# 7-JTAG_Power.net
KiCad netlist of a schematic drawn in Altium Designer
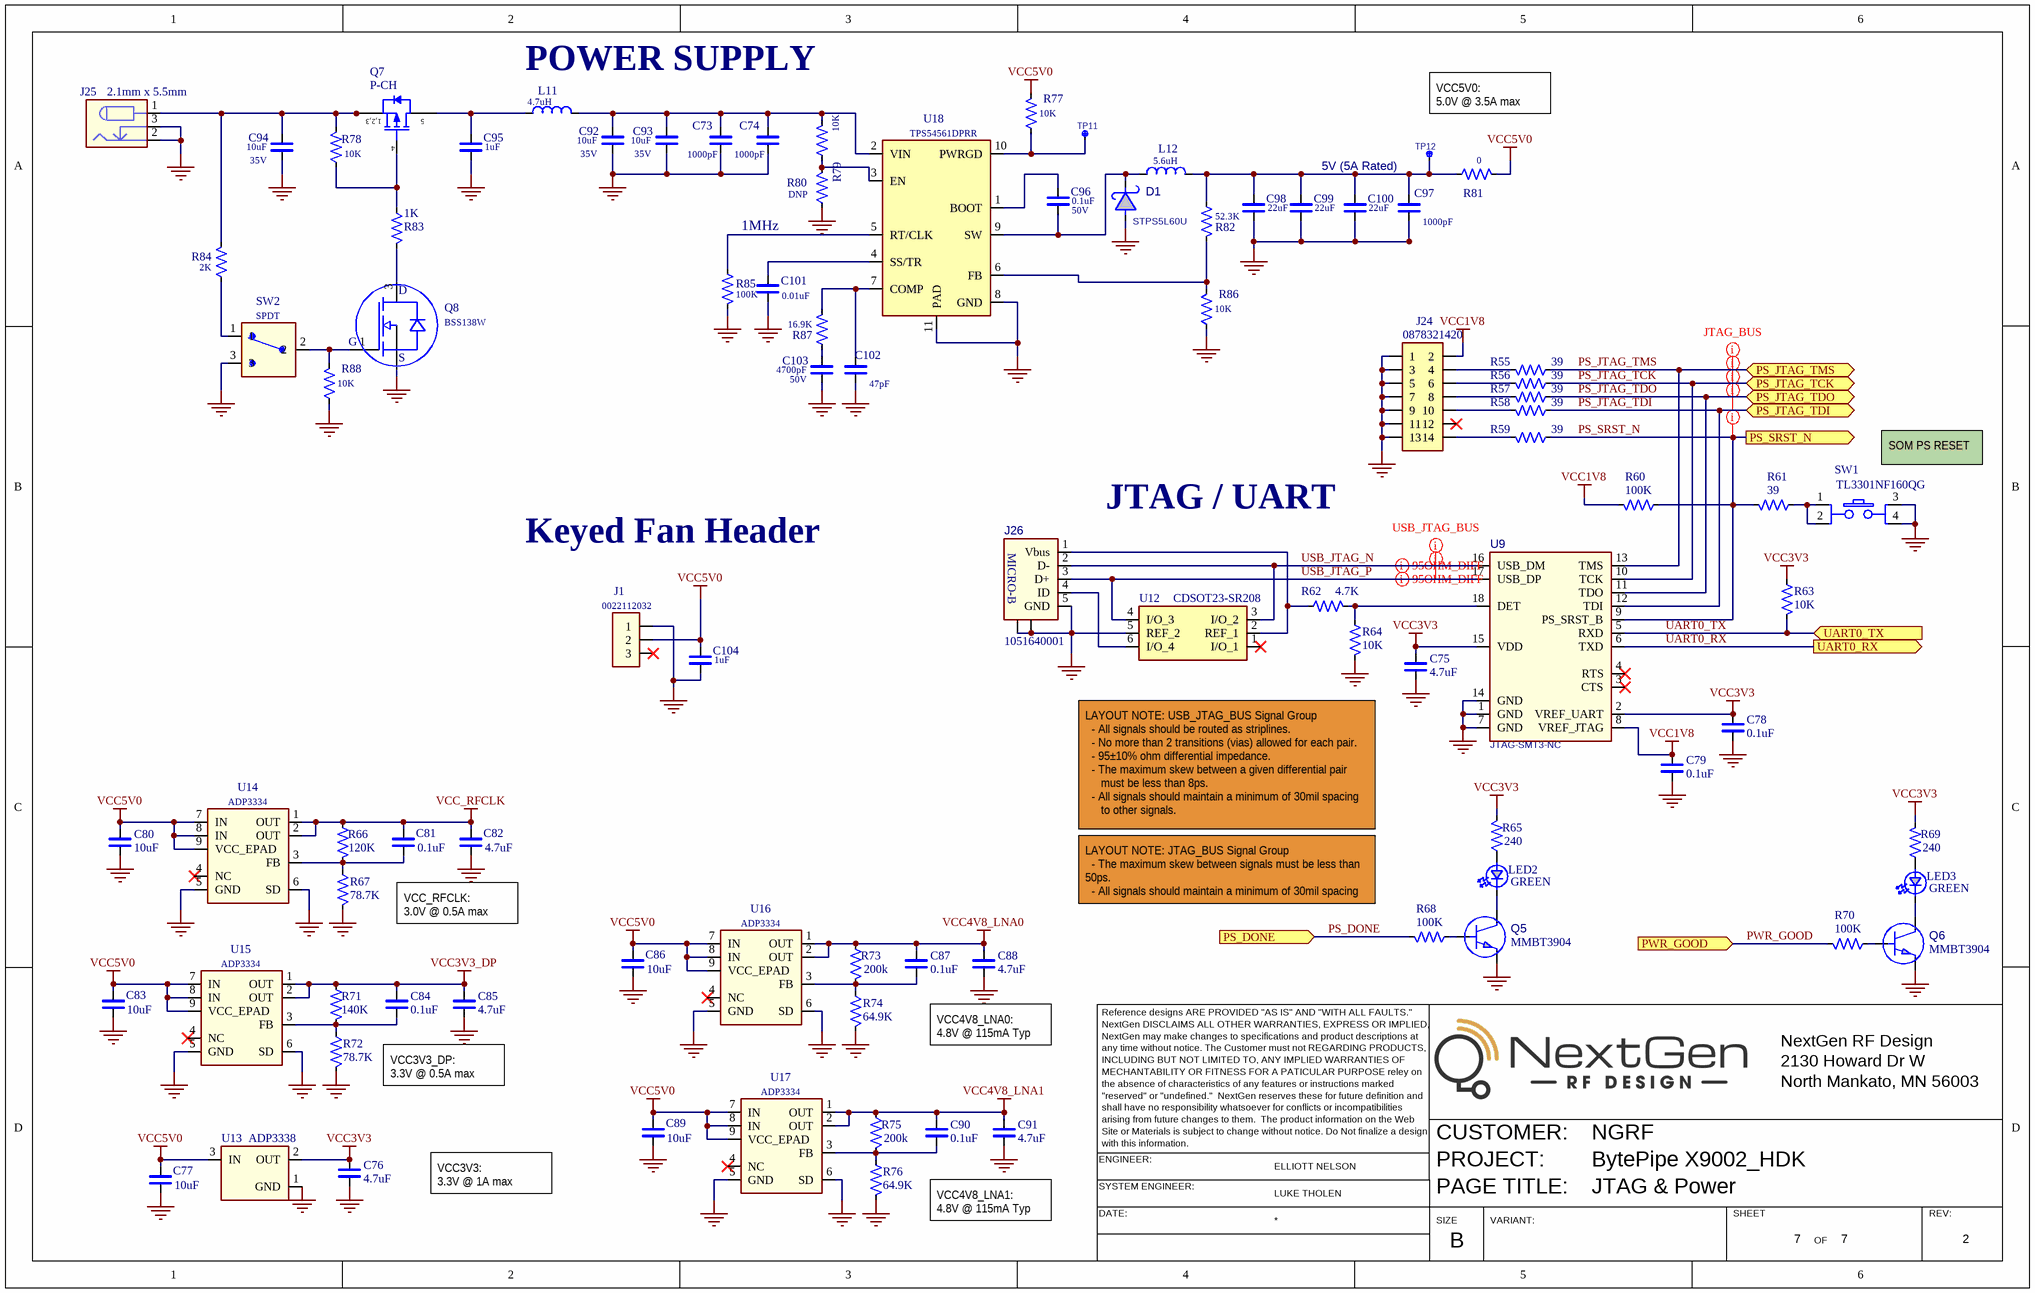
[diagram p0: 7-JTAG & Power.SchDoc]

(export (version "E")
  (design (tool "Eeschema 10.0.6"))
  (components
    (comp (ref "C73")
      (value "1000pF")
      (footprint "SM/0402/CAP")
      (description "CAP CER 1000PF 50V C0G/NP0 0402")
      (libsource (lib "NextGenRF_Symbols_SMT") (part "CAP_CERAMIC_0402"))
    )
    (comp (ref "C74")
      (value "1000pF")
      (footprint "SM/0402/CAP")
      (description "CAP CER 1000PF 50V C0G/NP0 0402")
      (libsource (lib "NextGenRF_Symbols_SMT") (part "CAP_CERAMIC_0402"))
    )
    (comp (ref "C75")
      (value "4.7uF")
      (footprint "SM/0402/CAP")
      (description "CAP CER 4.7UF 10V X5R 0402")
      (fields (field (name "Comment") "CAP_CERAMIC_0402"))
      (libsource (lib "NextGenRF_Symbols_SMT") (part "CAP_CERAMIC_0402"))
    )
    (comp (ref "C76")
      (value "4.7uF")
      (footprint "SM/0402/CAP")
      (description "CAP CER 4.7UF 10V X5R 0402")
      (fields (field (name "Comment") "CAP_CERAMIC_0402"))
      (libsource (lib "NextGenRF_Symbols_SMT") (part "CAP_CERAMIC_0402"))
    )
    (comp (ref "C77")
      (value "10uF")
      (footprint "SM/0402/CAP")
      (description "10µF ±20% 10V Ceramic Capacitor X5R 0402 (1005 Metric)")
      (fields (field (name "Comment") "CAP_CERAMIC_0402"))
      (libsource (lib "NextGenRF_Symbols_SMT") (part "CAP_CERAMIC_0402"))
    )
    (comp (ref "C78")
      (value "0.1uF")
      (footprint "SM/0402/CAP")
      (description "CAP CER 0.1UF 25V X7R 0402")
      (fields (field (name "Comment") "CAP_CERAMIC_0402"))
      (libsource (lib "NextGenRF_Symbols_SMT") (part "CAP_CERAMIC_0402"))
    )
    (comp (ref "C79")
      (value "0.1uF")
      (footprint "SM/0402/CAP")
      (description "CAP CER 0.1UF 25V X7R 0402")
      (fields (field (name "Comment") "CAP_CERAMIC_0402"))
      (libsource (lib "NextGenRF_Symbols_SMT") (part "CAP_CERAMIC_0402"))
    )
    (comp (ref "C80")
      (value "10uF")
      (footprint "SM/0402/CAP")
      (description "10µF ±20% 10V Ceramic Capacitor X5R 0402 (1005 Metric)")
      (fields (field (name "Comment") "CAP_CERAMIC_0402"))
      (libsource (lib "NextGenRF_Symbols_SMT") (part "CAP_CERAMIC_0402"))
    )
    (comp (ref "C81")
      (value "0.1uF")
      (footprint "SM/0402/CAP")
      (description "CAP CER 0.1UF 25V X7R 0402")
      (fields (field (name "Comment") "CAP_CERAMIC_0402"))
      (libsource (lib "NextGenRF_Symbols_SMT") (part "CAP_CERAMIC_0402"))
    )
    (comp (ref "C82")
      (value "4.7uF")
      (footprint "SM/0402/CAP")
      (description "CAP CER 4.7UF 10V X5R 0402")
      (fields (field (name "Comment") "CAP_CERAMIC_0402"))
      (libsource (lib "NextGenRF_Symbols_SMT") (part "CAP_CERAMIC_0402"))
    )
    (comp (ref "C83")
      (value "10uF")
      (footprint "SM/0402/CAP")
      (description "10µF ±20% 10V Ceramic Capacitor X5R 0402 (1005 Metric)")
      (fields (field (name "Comment") "CAP_CERAMIC_0402"))
      (libsource (lib "NextGenRF_Symbols_SMT") (part "CAP_CERAMIC_0402"))
    )
    (comp (ref "C84")
      (value "0.1uF")
      (footprint "SM/0402/CAP")
      (description "CAP CER 0.1UF 25V X7R 0402")
      (fields (field (name "Comment") "CAP_CERAMIC_0402"))
      (libsource (lib "NextGenRF_Symbols_SMT") (part "CAP_CERAMIC_0402"))
    )
    (comp (ref "C85")
      (value "4.7uF")
      (footprint "SM/0402/CAP")
      (description "CAP CER 4.7UF 10V X5R 0402")
      (fields (field (name "Comment") "CAP_CERAMIC_0402"))
      (libsource (lib "NextGenRF_Symbols_SMT") (part "CAP_CERAMIC_0402"))
    )
    (comp (ref "C86")
      (value "10uF")
      (footprint "SM/0402/CAP")
      (description "10µF ±20% 10V Ceramic Capacitor X5R 0402 (1005 Metric)")
      (fields (field (name "Comment") "CAP_CERAMIC_0402"))
      (libsource (lib "NextGenRF_Symbols_SMT") (part "CAP_CERAMIC_0402"))
    )
    (comp (ref "C87")
      (value "0.1uF")
      (footprint "SM/0402/CAP")
      (description "CAP CER 0.1UF 25V X7R 0402")
      (fields (field (name "Comment") "CAP_CERAMIC_0402"))
      (libsource (lib "NextGenRF_Symbols_SMT") (part "CAP_CERAMIC_0402"))
    )
    (comp (ref "C88")
      (value "4.7uF")
      (footprint "SM/0402/CAP")
      (description "CAP CER 4.7UF 10V X5R 0402")
      (fields (field (name "Comment") "CAP_CERAMIC_0402"))
      (libsource (lib "NextGenRF_Symbols_SMT") (part "CAP_CERAMIC_0402"))
    )
    (comp (ref "C89")
      (value "10uF")
      (footprint "SM/0402/CAP")
      (description "10µF ±20% 10V Ceramic Capacitor X5R 0402 (1005 Metric)")
      (fields (field (name "Comment") "CAP_CERAMIC_0402"))
      (libsource (lib "NextGenRF_Symbols_SMT") (part "CAP_CERAMIC_0402"))
    )
    (comp (ref "C90")
      (value "0.1uF")
      (footprint "SM/0402/CAP")
      (description "CAP CER 0.1UF 25V X7R 0402")
      (fields (field (name "Comment") "CAP_CERAMIC_0402"))
      (libsource (lib "NextGenRF_Symbols_SMT") (part "CAP_CERAMIC_0402"))
    )
    (comp (ref "C91")
      (value "4.7uF")
      (footprint "SM/0402/CAP")
      (description "CAP CER 4.7UF 10V X5R 0402")
      (fields (field (name "Comment") "CAP_CERAMIC_0402"))
      (libsource (lib "NextGenRF_Symbols_SMT") (part "CAP_CERAMIC_0402"))
    )
    (comp (ref "C92")
      (value "10uF")
      (footprint "NGRF_SMT_Footprints:SM/0805/CAP")
      (description "CAP CER 10UF 35V X5R 0805")
      (fields (field (name "VOLT") "35V") (field (name "Comment") "CAP_CERAMIC_0805"))
      (libsource (lib "NextGenRF_Symbols_SMT") (part "CAP_CERAMIC_0805"))
    )
    (comp (ref "C93")
      (value "10uF")
      (footprint "NGRF_SMT_Footprints:SM/0805/CAP")
      (description "CAP CER 10UF 35V X5R 0805")
      (fields (field (name "VOLT") "35V") (field (name "Comment") "CAP_CERAMIC_0805"))
      (libsource (lib "NextGenRF_Symbols_SMT") (part "CAP_CERAMIC_0805"))
    )
    (comp (ref "C94")
      (value "10uF")
      (footprint "NGRF_SMT_Footprints:SM/0805/CAP")
      (description "CAP CER 10UF 35V X5R 0805")
      (fields (field (name "VOLT") "35V") (field (name "Comment") "CAP_CERAMIC_0805"))
      (libsource (lib "NextGenRF_Symbols_SMT") (part "CAP_CERAMIC_0805"))
    )
    (comp (ref "C95")
      (value "1uF")
      (footprint "NGRF_SMT_Footprints:SM/0603/CAP")
      (fields (field (name "Comment") "CAP_CERAMIC_0603"))
      (libsource (lib "NextGenRF_Symbols_SMT") (part "CAP_CERAMIC_0603"))
    )
    (comp (ref "C96")
      (value "0.1uF")
      (footprint "SM/0402/CAP")
      (description "CAP CER 0.1UF 50V X7R 0402")
      (fields (field (name "VOLT") "50V") (field (name "Comment") "CAP_CERAMIC_0402"))
      (libsource (lib "NextGenRF_Symbols_SMT") (part "CAP_CERAMIC_0402"))
    )
    (comp (ref "C97")
      (value "1000pF")
      (footprint "SM/0402/CAP")
      (description "CAP CER 1000PF 50V C0G/NP0 0402")
      (libsource (lib "NextGenRF_Symbols_SMT") (part "CAP_CERAMIC_0402"))
    )
    (comp (ref "C98")
      (value "22uF")
      (footprint "NGRF_SMT_Footprints:SM/0805/CAP")
      (description "CAP CER 22UF 16V X5R 0805")
      (fields (field (name "Comment") "CAP_CERAMIC_0805"))
      (libsource (lib "NextGenRF_Symbols_SMT") (part "CAP_CERAMIC_0805"))
    )
    (comp (ref "C99")
      (value "22uF")
      (footprint "NGRF_SMT_Footprints:SM/0805/CAP")
      (description "CAP CER 22UF 16V X5R 0805")
      (fields (field (name "Comment") "CAP_CERAMIC_0805"))
      (libsource (lib "NextGenRF_Symbols_SMT") (part "CAP_CERAMIC_0805"))
    )
    (comp (ref "C100")
      (value "22uF")
      (footprint "NGRF_SMT_Footprints:SM/0805/CAP")
      (description "CAP CER 22UF 16V X5R 0805")
      (fields (field (name "Comment") "CAP_CERAMIC_0805"))
      (libsource (lib "NextGenRF_Symbols_SMT") (part "CAP_CERAMIC_0805"))
    )
    (comp (ref "C101")
      (value "0.01uF")
      (footprint "SM/0402/CAP")
      (description "CAP CER 10000PF 50V X7R 0402")
      (libsource (lib "NextGenRF_Symbols_SMT") (part "CAP_CERAMIC_0402"))
    )
    (comp (ref "C102")
      (value "47pF")
      (footprint "SM/0402/CAP")
      (description "CAP CER 47PF 50V C0G/NP0 0402")
      (libsource (lib "NextGenRF_Symbols_SMT") (part "CAP_CERAMIC_0402"))
    )
    (comp (ref "C103")
      (value "4700pF")
      (footprint "SM/0402/CAP")
      (description "CAP CER 4700PF 50V X7R 0402")
      (fields (field (name "VOLT") "50V"))
      (libsource (lib "NextGenRF_Symbols_SMT") (part "CAP_CERAMIC_0402"))
    )
    (comp (ref "C104")
      (value "1uF")
      (footprint "NGRF_SMT_Footprints:SM/0603/CAP")
      (fields (field (name "Comment") "CAP_CERAMIC_0603"))
      (libsource (lib "NextGenRF_Symbols_SMT") (part "CAP_CERAMIC_0603"))
    )
    (comp (ref "D1")
      (value "STPS5L60U")
      (footprint "NGRF_SMT_Footprints:SM/DO-214AA/SMB_A")
      (description "DIODE SCHOTTKY 60V 5A SMB")
      (fields (field (name "Comment") "DIODE_SCHOTTKY SMB"))
      (libsource (lib "NextGenRF_Symbols_SMT") (part "DIODE_SCHOTTKY SMB"))
    )
    (comp (ref "J1")
      (value "0022112032")
      (footprint "CON/MLX/0022112032/3P")
      (description "Connector Header Through Hole 3 position 0.100\" (2.54mm).  Molex KK 100 Series.")
      (libsource (lib "NextGenRF_Symbols_TH") (part "CON_100SP_1X3P_MLX_KK100"))
    )
    (comp (ref "J24")
      (value "0878321420")
      (footprint "SM/CON/MLX/0878321420")
      (description "Connector Header Surface Mount 14 position 0.079\" (2.00mm)")
      (fields (field (name "Comment") "CON_MOLEX_0878321420_14P"))
      (libsource (lib "NextGenRF_Symbols_SMT") (part "CON_MOLEX_0878321420_14P"))
    )
    (comp (ref "J25")
      (value "2.1mm x 5.5mm")
      (footprint "NGRF_Thru-Hole_Footprints:CON/WURTH/694106301002")
      (description "Wurth DC power jack, 2.1mm pin, right angle")
      (fields (field (name "Comment") "CON_WURTH_694106301002"))
      (libsource (lib "NextGenRF_Symbols_TH") (part "CON_WURTH_694106301002"))
    )
    (comp (ref "J26")
      (value "1051640001")
      (footprint "SM/CON/USB/MICRO B RA")
      (description "USB MICRO-B RIGHT ANGLE, MOLEX 1051640001")
      (fields (field (name "Comment") "CON_USB_MICRO-B_RA"))
      (libsource (lib "NextGenRF_Symbols_SMT") (part "CON_USB_MICRO-B_RA"))
    )
    (comp (ref "L11")
      (value "4.7uH")
      (footprint "SM/IND/COILCRAFT/XAL4020")
      (description "Fixed Inductors 4.7uH 20% 5.1A 44.1mOhms AEC-Q200")
      (fields (field (name "Comment") "IND_COILCRAFT_XAL4020"))
      (libsource (lib "NextGenRF_Symbols_SMT") (part "IND_COILCRAFT_XAL4020"))
    )
    (comp (ref "L12")
      (value "5.6uH")
      (footprint "SM/IND/COILCRAFT/XAL7030")
      (fields (field (name "Comment") "IND_COILCRAFT_XAL7030"))
      (libsource (lib "NextGenRF_Symbols_SMT") (part "IND_COILCRAFT_XAL7030"))
    )
    (comp (ref "LED2")
      (value "GREEN")
      (footprint "NGRF_SMT_Footprints:SM/LED_0603")
      (description "LED-0603")
      (fields (field (name "Comment") "LED_0603"))
      (libsource (lib "NextGenRF_Symbols_SMT") (part "LED_0603"))
    )
    (comp (ref "LED3")
      (value "GREEN")
      (footprint "NGRF_SMT_Footprints:SM/LED_0603")
      (description "LED-0603")
      (fields (field (name "Comment") "LED_0603"))
      (libsource (lib "NextGenRF_Symbols_SMT") (part "LED_0603"))
    )
    (comp (ref "Q5")
      (value "MMBT3904")
      (footprint "NGRF_SMT_Footprints:SM/SOT23_A")
      (description "Bipolar (BJT) Transistor NPN 40V 200mA 300MHz 300mW Surface Mount SOT-23-3 (TO-236)")
      (fields (field (name "Comment") "TRANSISTOR_NPN_SOT23"))
      (libsource (lib "NextGenRF_Symbols_SMT") (part "TRANSISTOR_NPN_SOT23"))
    )
    (comp (ref "Q6")
      (value "MMBT3904")
      (footprint "NGRF_SMT_Footprints:SM/SOT23_A")
      (description "Bipolar (BJT) Transistor NPN 40V 200mA 300MHz 300mW Surface Mount SOT-23-3 (TO-236)")
      (fields (field (name "Comment") "TRANSISTOR_NPN_SOT23"))
      (libsource (lib "NextGenRF_Symbols_SMT") (part "TRANSISTOR_NPN_SOT23"))
    )
    (comp (ref "Q7")
      (value "P-CH")
      (footprint "SM/POWERPAK/VISHAY/SO-8")
      (description "P-Channel 20 V 60A (Tc) 6.25W (Ta), 104W (Tc) Surface Mount PowerPAK® SO-8")
      (fields (field (name "Comment") "MOSFET P-CH 20V 60A PPAK SO-8"))
      (libsource (lib "NextGenRF_Symbols_SMT") (part "FET_P-CHANNEL_PPAK-SO-8"))
    )
    (comp (ref "Q8")
      (value "BSS138W")
      (footprint "SM/SOT323_A")
      (description "FET, N-Channel, SC70/SOT323")
      (fields (field (name "Comment") "FET_N-CHANNEL_SC70"))
      (libsource (lib "NextGenRF_Symbols_SMT") (part "FET_N-CHANNEL_SC70"))
    )
    (comp (ref "R55")
      (value "39")
      (footprint "SM/0402/RES")
      (description "RES SMD 39 OHM 1% 1/10W 0402")
      (fields (field (name "Comment") "RES_0402_A"))
      (libsource (lib "NextGenRF_Symbols_SMT") (part "RES_0402_A"))
    )
    (comp (ref "R56")
      (value "39")
      (footprint "SM/0402/RES")
      (description "RES SMD 39 OHM 1% 1/10W 0402")
      (fields (field (name "Comment") "RES_0402_A"))
      (libsource (lib "NextGenRF_Symbols_SMT") (part "RES_0402_A"))
    )
    (comp (ref "R57")
      (value "39")
      (footprint "SM/0402/RES")
      (description "RES SMD 39 OHM 1% 1/10W 0402")
      (fields (field (name "Comment") "RES_0402_A"))
      (libsource (lib "NextGenRF_Symbols_SMT") (part "RES_0402_A"))
    )
    (comp (ref "R58")
      (value "39")
      (footprint "SM/0402/RES")
      (description "RES SMD 39 OHM 1% 1/10W 0402")
      (fields (field (name "Comment") "RES_0402_A"))
      (libsource (lib "NextGenRF_Symbols_SMT") (part "RES_0402_A"))
    )
    (comp (ref "R59")
      (value "39")
      (footprint "SM/0402/RES")
      (description "RES SMD 39 OHM 1% 1/10W 0402")
      (fields (field (name "Comment") "RES_0402_A"))
      (libsource (lib "NextGenRF_Symbols_SMT") (part "RES_0402_A"))
    )
    (comp (ref "R60")
      (value "100K")
      (footprint "SM/0402/RES")
      (description "RES SMD 100K OHM 1% 1/10W 0402")
      (fields (field (name "Comment") "RES_0402_A"))
      (libsource (lib "NextGenRF_Symbols_SMT") (part "RES_0402_A"))
    )
    (comp (ref "R61")
      (value "39")
      (footprint "SM/0402/RES")
      (description "RES SMD 39 OHM 1% 1/10W 0402")
      (fields (field (name "Comment") "RES_0402_A"))
      (libsource (lib "NextGenRF_Symbols_SMT") (part "RES_0402_A"))
    )
    (comp (ref "R62")
      (value "4.7K")
      (footprint "SM/0402/RES")
      (description "RES SMD 4.7K OHM 1% 1/10W 0402")
      (fields (field (name "Comment") "RES_0402_A"))
      (libsource (lib "NextGenRF_Symbols_SMT") (part "RES_0402_A"))
    )
    (comp (ref "R63")
      (value "10K")
      (footprint "SM/0402/RES")
      (fields (field (name "Comment") "RES_0402_A"))
      (libsource (lib "NextGenRF_Symbols_SMT") (part "RES_0402_A"))
    )
    (comp (ref "R64")
      (value "10K")
      (footprint "SM/0402/RES")
      (fields (field (name "Comment") "RES_0402_A"))
      (libsource (lib "NextGenRF_Symbols_SMT") (part "RES_0402_A"))
    )
    (comp (ref "R65")
      (value "240")
      (footprint "SM/0402/RES")
      (description "RES SMD 240 OHM 1% 1/10W 0402")
      (fields (field (name "Comment") "RES_0402_A"))
      (libsource (lib "NextGenRF_Symbols_SMT") (part "RES_0402_A"))
    )
    (comp (ref "R66")
      (value "120K")
      (footprint "SM/0402/RES")
      (description "RES 120K OHM 1% 1/10W 0402 SMD")
      (fields (field (name "Comment") "RES_0402_A"))
      (libsource (lib "NextGenRF_Symbols_SMT") (part "RES_0402_A"))
    )
    (comp (ref "R67")
      (value "78.7K")
      (footprint "SM/0402/RES")
      (description "RES SMD 78.7K OHM 1% 1/10W 0402")
      (fields (field (name "Comment") "RES_0402_A"))
      (libsource (lib "NextGenRF_Symbols_SMT") (part "RES_0402_A"))
    )
    (comp (ref "R68")
      (value "100K")
      (footprint "SM/0402/RES")
      (description "RES SMD 100K OHM 1% 1/10W 0402")
      (fields (field (name "Comment") "RES_0402_A"))
      (libsource (lib "NextGenRF_Symbols_SMT") (part "RES_0402_A"))
    )
    (comp (ref "R69")
      (value "240")
      (footprint "SM/0402/RES")
      (description "RES SMD 240 OHM 1% 1/10W 0402")
      (fields (field (name "Comment") "RES_0402_A"))
      (libsource (lib "NextGenRF_Symbols_SMT") (part "RES_0402_A"))
    )
    (comp (ref "R70")
      (value "100K")
      (footprint "SM/0402/RES")
      (description "RES SMD 100K OHM 1% 1/10W 0402")
      (fields (field (name "Comment") "RES_0402_A"))
      (libsource (lib "NextGenRF_Symbols_SMT") (part "RES_0402_A"))
    )
    (comp (ref "R71")
      (value "140K")
      (footprint "SM/0402/RES")
      (description "RES SMD 140K OHM 1% 1/10W 0402")
      (fields (field (name "Comment") "RES_0402_A"))
      (libsource (lib "NextGenRF_Symbols_SMT") (part "RES_0402_A"))
    )
    (comp (ref "R72")
      (value "78.7K")
      (footprint "SM/0402/RES")
      (description "RES SMD 78.7K OHM 1% 1/10W 0402")
      (fields (field (name "Comment") "RES_0402_A"))
      (libsource (lib "NextGenRF_Symbols_SMT") (part "RES_0402_A"))
    )
    (comp (ref "R73")
      (value "200k")
      (footprint "SM/0402/RES")
      (description "RES SMD 200K OHM 1% 1/10W 0402")
      (fields (field (name "Comment") "RES_0402_A"))
      (libsource (lib "NextGenRF_Symbols_SMT") (part "RES_0402_A"))
    )
    (comp (ref "R74")
      (value "64.9K")
      (footprint "SM/0402/RES")
      (description "RES SMD 64.9K OHM 1% 1/10W 0402")
      (fields (field (name "Comment") "RES_0402_A"))
      (libsource (lib "NextGenRF_Symbols_SMT") (part "RES_0402_A"))
    )
    (comp (ref "R75")
      (value "200k")
      (footprint "SM/0402/RES")
      (description "RES SMD 200K OHM 1% 1/10W 0402")
      (fields (field (name "Comment") "RES_0402_A"))
      (libsource (lib "NextGenRF_Symbols_SMT") (part "RES_0402_A"))
    )
    (comp (ref "R76")
      (value "64.9K")
      (footprint "SM/0402/RES")
      (description "RES SMD 64.9K OHM 1% 1/10W 0402")
      (fields (field (name "Comment") "RES_0402_A"))
      (libsource (lib "NextGenRF_Symbols_SMT") (part "RES_0402_A"))
    )
    (comp (ref "R77")
      (value "10K")
      (footprint "SM/0402/RES")
      (description "RES SMD 10K OHM 1% 1/10W 0402")
      (fields (field (name "Comment") "RES_0402_A"))
      (libsource (lib "NextGenRF_Symbols_SMT") (part "RES_0402_A"))
    )
    (comp (ref "R78")
      (value "10K")
      (footprint "SM/0402/RES")
      (description "RES SMD 10K OHM 1% 1/10W 0402")
      (fields (field (name "Comment") "RES_0402_A"))
      (libsource (lib "NextGenRF_Symbols_SMT") (part "RES_0402_A"))
    )
    (comp (ref "R79")
      (value "10K")
      (footprint "SM/0402/RES")
      (description "RES SMD 10K OHM 1% 1/10W 0402")
      (fields (field (name "Comment") "RES_0402_A"))
      (libsource (lib "NextGenRF_Symbols_SMT") (part "RES_0402_A"))
    )
    (comp (ref "R80")
      (value "DNP")
      (footprint "SM/0402/RES")
      (fields (field (name "Comment") "RES_0402_A"))
      (libsource (lib "NextGenRF_Symbols_SMT") (part "RES_0402_A"))
    )
    (comp (ref "R81")
      (value "0")
      (footprint "NGRF_SMT_Footprints:SM/0805/RES")
      (description "RES SMD 0 OHM JUMPER 1/8W 0805")
      (fields (field (name "Comment") "RES_0805_A"))
      (libsource (lib "NextGenRF_Symbols_SMT") (part "RES_0805_A"))
    )
    (comp (ref "R82")
      (value "52.3K")
      (footprint "SM/0402/RES")
      (description "RES SMD 52.3K OHM 1% 1/10W 0402")
      (fields (field (name "Comment") "RES_0402_A"))
      (libsource (lib "NextGenRF_Symbols_SMT") (part "RES_0402_A"))
    )
    (comp (ref "R83")
      (value "1K")
      (footprint "SM/0402/RES")
      (description "RES SMD 1K OHM 1% 1/10W 0402")
      (fields (field (name "Comment") "RES_0402_A"))
      (libsource (lib "NextGenRF_Symbols_SMT") (part "RES_0402_A"))
    )
    (comp (ref "R84")
      (value "2K")
      (footprint "SM/0402/RES")
      (description "RES SMD 2 KOHM 1% 1/5W 0402")
      (fields (field (name "Comment") "RES_0402_A"))
      (libsource (lib "NextGenRF_Symbols_SMT") (part "RES_0402_A"))
    )
    (comp (ref "R85")
      (value "100K")
      (footprint "SM/0402/RES")
      (description "RES SMD 100K OHM 1% 1/10W 0402")
      (fields (field (name "Comment") "RES_0402_A"))
      (libsource (lib "NextGenRF_Symbols_SMT") (part "RES_0402_A"))
    )
    (comp (ref "R86")
      (value "10K")
      (footprint "SM/0402/RES")
      (description "RES SMD 10K OHM 1% 1/10W 0402")
      (fields (field (name "Comment") "RES_0402_A"))
      (libsource (lib "NextGenRF_Symbols_SMT") (part "RES_0402_A"))
    )
    (comp (ref "R87")
      (value "16.9K")
      (footprint "SM/0402/RES")
      (description "RES SMD 16.9K OHM 1% 1/10W 0402")
      (fields (field (name "Comment") "RES_0402_A"))
      (libsource (lib "NextGenRF_Symbols_SMT") (part "RES_0402_A"))
    )
    (comp (ref "R88")
      (value "10K")
      (footprint "SM/0402/RES")
      (description "RES SMD 10K OHM 1% 1/10W 0402")
      (fields (field (name "Comment") "RES_0402_A"))
      (libsource (lib "NextGenRF_Symbols_SMT") (part "RES_0402_A"))
    )
    (comp (ref "SW1")
      (value "TL3301NF160QG")
      (footprint "SM/SWITCH/E-SWITCH/SPST")
      (description "Tactile Switch SPST-NO Top Actuated Surface Mount")
      (fields (field (name "Comment") "SWITCH_E-SWITCH_TACTILE_SPST"))
      (libsource (lib "NextGenRF_Symbols_SMT") (part "SWITCH_E-SWITCH_TACTILE_SPST"))
    )
    (comp (ref "SW2")
      (value "SPDT")
      (footprint "SWITCH/NIDEC/SPDT/AS1D-2M-10-Z")
      (description "SWITCH SLIDE SPDT 50MA 48V")
      (fields (field (name "Comment") "AS1D-2M-10-Z"))
      (libsource (lib "NextGenRF_Symbols_TH") (part "SWITCH_SLIDE_NIDEC_SPDT"))
    )
    (comp (ref "TP11")
      (value "TESTPOINT_030")
      (footprint "SM/TESTPOINT/30MIL")
      (libsource (lib "NextGenRF_Symbols_SMT") (part "TESTPOINT_030"))
    )
    (comp (ref "TP12")
      (value "TESTPOINT_030")
      (footprint "SM/TESTPOINT/30MIL")
      (libsource (lib "NextGenRF_Symbols_SMT") (part "TESTPOINT_030"))
    )
    (comp (ref "U9")
      (value "JTAG-SMT3-NC")
      (footprint "SM/MODULE/DIGILENT/JTAG-SMT3")
      (description "SMT Programming module for Xilinx FPGAs.")
      (fields (field (name "Comment") "MODULE_JTAG-SMT3-NC_18P"))
      (libsource (lib "NextGenRF_Symbols_SMT") (part "MODULE_JTAG-SMT3-NC_18P"))
    )
    (comp (ref "U12")
      (value "CDSOT23-SR208")
      (footprint "SM/SOT23-6_C")
      (description "Clamp Ipp Tvs Diode Surface Mount SOT-23-6.")
      (fields (field (name "Comment") "TVS_CDSOT23_SOT23-6_C"))
      (libsource (lib "NextGenRF_Symbols_SMT") (part "TVS_CDSOT23_SOT23-6_C"))
    )
    (comp (ref "U13")
      (value "ADP3338")
      (footprint "SM/SOT223-3_B")
      (description "Linear Voltage Regulator IC 3.3V Output 1A SOT-223-3")
      (fields (field (name "Comment") "REG_ADP3338_SOT223-3"))
      (libsource (lib "NextGenRF_Symbols_SMT") (part "REG_ADP3338_SOT223-3"))
    )
    (comp (ref "U14")
      (value "ADP3334")
      (footprint "SM/DFN8/3x3MM_B")
      (description "Linear Voltage Regulator IC  1 Output  500mA 8-LFCSP-WD (3x3)")
      (fields (field (name "Comment") "REG_ADP334_DFN-8"))
      (libsource (lib "NextGenRF_Symbols_SMT") (part "REG_ADP334_DFN-8"))
    )
    (comp (ref "U15")
      (value "ADP3334")
      (footprint "SM/DFN8/3x3MM_B")
      (description "Linear Voltage Regulator IC  1 Output  500mA 8-LFCSP-WD (3x3)")
      (fields (field (name "Comment") "REG_ADP334_DFN-8"))
      (libsource (lib "NextGenRF_Symbols_SMT") (part "REG_ADP334_DFN-8"))
    )
    (comp (ref "U16")
      (value "ADP3334")
      (footprint "SM/DFN8/3x3MM_B")
      (description "Linear Voltage Regulator IC  1 Output  500mA 8-LFCSP-WD (3x3)")
      (fields (field (name "Comment") "REG_ADP334_DFN-8"))
      (libsource (lib "NextGenRF_Symbols_SMT") (part "REG_ADP334_DFN-8"))
    )
    (comp (ref "U17")
      (value "ADP3334")
      (footprint "SM/DFN8/3x3MM_B")
      (description "Linear Voltage Regulator IC  1 Output  500mA 8-LFCSP-WD (3x3)")
      (fields (field (name "Comment") "REG_ADP334_DFN-8"))
      (libsource (lib "NextGenRF_Symbols_SMT") (part "REG_ADP334_DFN-8"))
    )
    (comp (ref "U18")
      (value "TPS54561DPRR")
      (footprint "SM/WSON10/4x4MM_A")
      (description "4.5-V to 60-V Input, 5-A, Step-Down DC-DC Converter with Soft-Start and Eco-mode")
      (fields (field (name "Comment") "REG_TPS54561_WSON-10"))
      (libsource (lib "NextGenRF_Symbols_SMT") (part "REG_TPS54561_WSON-10"))
    )
  )
  (nets
    (net (code "1") (name "/PS_DONE") (class "Default")
      (node (ref "R68") (pin "2") (pinfunction "2_2") (pintype "passive"))
    )
    (net (code "2") (name "/PS_JTAG_TCK") (class "Default")
      (node (ref "R56") (pin "1") (pinfunction "1_1") (pintype "passive"))
      (node (ref "U9") (pin "10") (pinfunction "TCK_10") (pintype "passive"))
    )
    (net (code "3") (name "/PS_JTAG_TDI") (class "Default")
      (node (ref "R58") (pin "1") (pinfunction "1_1") (pintype "passive"))
      (node (ref "U9") (pin "12") (pinfunction "TDI_12") (pintype "passive"))
    )
    (net (code "4") (name "/PS_JTAG_TDO") (class "Default")
      (node (ref "R57") (pin "1") (pinfunction "1_1") (pintype "passive"))
      (node (ref "U9") (pin "11") (pinfunction "TDO_11") (pintype "passive"))
    )
    (net (code "5") (name "/PS_JTAG_TMS") (class "Default")
      (node (ref "R55") (pin "1") (pinfunction "1_1") (pintype "passive"))
      (node (ref "U9") (pin "13") (pinfunction "TMS_13") (pintype "passive"))
    )
    (net (code "6") (name "/PS_SRST_N") (class "Default")
      (node (ref "R59") (pin "1") (pinfunction "1_1") (pintype "passive"))
      (node (ref "R60") (pin "1") (pinfunction "1_1") (pintype "passive"))
      (node (ref "R61") (pin "2") (pinfunction "2_2") (pintype "passive"))
      (node (ref "U9") (pin "9") (pinfunction "PS_SRST_B_9") (pintype "passive"))
    )
    (net (code "7") (name "/PWR_GOOD") (class "Default")
      (node (ref "R70") (pin "2") (pinfunction "2_2") (pintype "passive"))
    )
    (net (code "8") (name "/UART0_RX") (class "Default")
      (node (ref "U9") (pin "6") (pinfunction "TXD_6") (pintype "passive"))
    )
    (net (code "9") (name "/UART0_TX") (class "Default")
      (node (ref "R63") (pin "2") (pinfunction "2_2") (pintype "passive"))
      (node (ref "U9") (pin "5") (pinfunction "RXD_5") (pintype "passive"))
    )
    (net (code "10") (name "/USB_JTAG_N") (class "Default")
      (node (ref "J26") (pin "2") (pinfunction "D-_2") (pintype "passive"))
      (node (ref "U12") (pin "3") (pinfunction "I/O_2_3") (pintype "passive"))
      (node (ref "U9") (pin "16") (pinfunction "USB_DM_16") (pintype "passive"))
    )
    (net (code "11") (name "/USB_JTAG_P") (class "Default")
      (node (ref "J26") (pin "3") (pinfunction "D+_3") (pintype "passive"))
      (node (ref "U12") (pin "4") (pinfunction "I/O_3_4") (pintype "passive"))
      (node (ref "U9") (pin "17") (pinfunction "USB_DP_17") (pintype "passive"))
    )
    (net (code "12") (name "GND") (class "Default")
      (node (ref "C100") (pin "2") (pinfunction "N2_2") (pintype "passive"))
      (node (ref "C101") (pin "1") (pinfunction "N1_1") (pintype "passive"))
      (node (ref "C102") (pin "1") (pinfunction "N1_1") (pintype "passive"))
      (node (ref "C103") (pin "2") (pinfunction "N2_2") (pintype "passive"))
      (node (ref "C104") (pin "2") (pinfunction "N2_2") (pintype "passive"))
      (node (ref "C73") (pin "1") (pinfunction "N1_1") (pintype "passive"))
      (node (ref "C74") (pin "1") (pinfunction "N1_1") (pintype "passive"))
      (node (ref "C75") (pin "2") (pinfunction "N2_2") (pintype "passive"))
      (node (ref "C76") (pin "2") (pinfunction "N2_2") (pintype "passive"))
      (node (ref "C77") (pin "2") (pinfunction "N2_2") (pintype "passive"))
      (node (ref "C78") (pin "2") (pinfunction "N2_2") (pintype "passive"))
      (node (ref "C79") (pin "2") (pinfunction "N2_2") (pintype "passive"))
      (node (ref "C80") (pin "2") (pinfunction "N2_2") (pintype "passive"))
      (node (ref "C82") (pin "2") (pinfunction "N2_2") (pintype "passive"))
      (node (ref "C83") (pin "2") (pinfunction "N2_2") (pintype "passive"))
      (node (ref "C85") (pin "2") (pinfunction "N2_2") (pintype "passive"))
      (node (ref "C86") (pin "2") (pinfunction "N2_2") (pintype "passive"))
      (node (ref "C88") (pin "2") (pinfunction "N2_2") (pintype "passive"))
      (node (ref "C89") (pin "2") (pinfunction "N2_2") (pintype "passive"))
      (node (ref "C91") (pin "2") (pinfunction "N2_2") (pintype "passive"))
      (node (ref "C92") (pin "2") (pinfunction "N2_2") (pintype "passive"))
      (node (ref "C93") (pin "2") (pinfunction "N2_2") (pintype "passive"))
      (node (ref "C94") (pin "2") (pinfunction "N2_2") (pintype "passive"))
      (node (ref "C95") (pin "2") (pinfunction "N2_2") (pintype "passive"))
      (node (ref "C97") (pin "1") (pinfunction "N1_1") (pintype "passive"))
      (node (ref "C98") (pin "2") (pinfunction "N2_2") (pintype "passive"))
      (node (ref "C99") (pin "2") (pinfunction "N2_2") (pintype "passive"))
      (node (ref "D1") (pin "2") (pinfunction "A_2") (pintype "passive"))
      (node (ref "J1") (pin "1") (pinfunction "1_1") (pintype "passive"))
      (node (ref "J24") (pin "1") (pinfunction "1_1") (pintype "passive"))
      (node (ref "J24") (pin "11") (pinfunction "11_11") (pintype "passive"))
      (node (ref "J24") (pin "13") (pinfunction "13_13") (pintype "passive"))
      (node (ref "J24") (pin "3") (pinfunction "3_3") (pintype "passive"))
      (node (ref "J24") (pin "5") (pinfunction "5_5") (pintype "passive"))
      (node (ref "J24") (pin "7") (pinfunction "7_7") (pintype "passive"))
      (node (ref "J24") (pin "9") (pinfunction "9_9") (pintype "passive"))
      (node (ref "J25") (pin "2") (pinfunction "2_2") (pintype "passive"))
      (node (ref "J25") (pin "3") (pinfunction "3_3") (pintype "passive"))
      (node (ref "J26") (pin "5") (pinfunction "GND_5") (pintype "passive"))
      (node (ref "J26") (pin "SH") (pinfunction "SH_SH") (pintype "passive"))
      (node (ref "J26") (pin "TH") (pinfunction "TH_TH") (pintype "passive"))
      (node (ref "Q5") (pin "2") (pinfunction "E_2") (pintype "passive"))
      (node (ref "Q6") (pin "2") (pinfunction "E_2") (pintype "passive"))
      (node (ref "Q8") (pin "2") (pinfunction "SOURCE_2") (pintype "passive"))
      (node (ref "R64") (pin "2") (pinfunction "2_2") (pintype "passive"))
      (node (ref "R67") (pin "1") (pinfunction "1_1") (pintype "passive"))
      (node (ref "R72") (pin "1") (pinfunction "1_1") (pintype "passive"))
      (node (ref "R74") (pin "1") (pinfunction "1_1") (pintype "passive"))
      (node (ref "R76") (pin "1") (pinfunction "1_1") (pintype "passive"))
      (node (ref "R80") (pin "1") (pinfunction "1_1") (pintype "passive"))
      (node (ref "R85") (pin "2") (pinfunction "2_2") (pintype "passive"))
      (node (ref "R86") (pin "2") (pinfunction "2_2") (pintype "passive"))
      (node (ref "R88") (pin "2") (pinfunction "2_2") (pintype "passive"))
      (node (ref "SW1") (pin "3") (pinfunction "3_3") (pintype "passive"))
      (node (ref "SW1") (pin "4") (pinfunction "4_4") (pintype "passive"))
      (node (ref "SW2") (pin "3") (pinfunction "3_3") (pintype "passive"))
      (node (ref "U12") (pin "5") (pinfunction "REF_2_5") (pintype "passive"))
      (node (ref "U13") (pin "1") (pinfunction "GND_1") (pintype "passive"))
      (node (ref "U14") (pin "5") (pinfunction "GND_5") (pintype "passive"))
      (node (ref "U14") (pin "6") (pinfunction "SD_6") (pintype "passive"))
      (node (ref "U15") (pin "5") (pinfunction "GND_5") (pintype "passive"))
      (node (ref "U15") (pin "6") (pinfunction "SD_6") (pintype "passive"))
      (node (ref "U16") (pin "5") (pinfunction "GND_5") (pintype "passive"))
      (node (ref "U16") (pin "6") (pinfunction "SD_6") (pintype "passive"))
      (node (ref "U17") (pin "5") (pinfunction "GND_5") (pintype "passive"))
      (node (ref "U17") (pin "6") (pinfunction "SD_6") (pintype "passive"))
      (node (ref "U18") (pin "11") (pinfunction "PAD_11") (pintype "passive"))
      (node (ref "U18") (pin "8") (pinfunction "GND_8") (pintype "passive"))
      (node (ref "U9") (pin "1") (pinfunction "GND_1") (pintype "passive"))
      (node (ref "U9") (pin "14") (pinfunction "GND_14") (pintype "passive"))
      (node (ref "U9") (pin "7") (pinfunction "GND_7") (pintype "passive"))
    )
    (net (code "13") (name "Net-(C73-N2)") (class "Default")
      (node (ref "C73") (pin "2") (pinfunction "N2_2") (pintype "passive"))
      (node (ref "C74") (pin "2") (pinfunction "N2_2") (pintype "passive"))
      (node (ref "C92") (pin "1") (pinfunction "N1_1") (pintype "passive"))
      (node (ref "C93") (pin "1") (pinfunction "N1_1") (pintype "passive"))
      (node (ref "L11") (pin "2") (pinfunction "N2_2") (pintype "passive"))
      (node (ref "R79") (pin "2") (pinfunction "2_2") (pintype "passive"))
      (node (ref "U18") (pin "2") (pinfunction "VIN_2") (pintype "passive"))
    )
    (net (code "14") (name "Net-(C81-N2)") (class "Default")
      (node (ref "C81") (pin "2") (pinfunction "N2_2") (pintype "passive"))
      (node (ref "R66") (pin "1") (pinfunction "1_1") (pintype "passive"))
      (node (ref "R67") (pin "2") (pinfunction "2_2") (pintype "passive"))
      (node (ref "U14") (pin "3") (pinfunction "FB_3") (pintype "passive"))
    )
    (net (code "15") (name "Net-(C84-N2)") (class "Default")
      (node (ref "C84") (pin "2") (pinfunction "N2_2") (pintype "passive"))
      (node (ref "R71") (pin "1") (pinfunction "1_1") (pintype "passive"))
      (node (ref "R72") (pin "2") (pinfunction "2_2") (pintype "passive"))
      (node (ref "U15") (pin "3") (pinfunction "FB_3") (pintype "passive"))
    )
    (net (code "16") (name "Net-(C87-N2)") (class "Default")
      (node (ref "C87") (pin "2") (pinfunction "N2_2") (pintype "passive"))
      (node (ref "R73") (pin "1") (pinfunction "1_1") (pintype "passive"))
      (node (ref "R74") (pin "2") (pinfunction "2_2") (pintype "passive"))
      (node (ref "U16") (pin "3") (pinfunction "FB_3") (pintype "passive"))
    )
    (net (code "17") (name "Net-(C90-N2)") (class "Default")
      (node (ref "C90") (pin "2") (pinfunction "N2_2") (pintype "passive"))
      (node (ref "R75") (pin "1") (pinfunction "1_1") (pintype "passive"))
      (node (ref "R76") (pin "2") (pinfunction "2_2") (pintype "passive"))
      (node (ref "U17") (pin "3") (pinfunction "FB_3") (pintype "passive"))
    )
    (net (code "18") (name "Net-(C94-N1)") (class "Default")
      (node (ref "C94") (pin "1") (pinfunction "N1_1") (pintype "passive"))
      (node (ref "J25") (pin "1") (pinfunction "1_1") (pintype "passive"))
      (node (ref "Q7") (pin "1") (pinfunction "SOURCE_1") (pintype "passive"))
      (node (ref "Q7") (pin "2") (pinfunction "SOURCE_2") (pintype "passive"))
      (node (ref "Q7") (pin "3") (pinfunction "SOURCE_3") (pintype "passive"))
      (node (ref "R78") (pin "1") (pinfunction "1_1") (pintype "passive"))
      (node (ref "R84") (pin "1") (pinfunction "1_1") (pintype "passive"))
    )
    (net (code "19") (name "Net-(C95-N1)") (class "Default")
      (node (ref "C95") (pin "1") (pinfunction "N1_1") (pintype "passive"))
      (node (ref "L11") (pin "1") (pinfunction "N1_1") (pintype "passive"))
      (node (ref "Q7") (pin "5") (pinfunction "DRAIN_5") (pintype "passive"))
    )
    (net (code "20") (name "Net-(C96-N1)") (class "Default")
      (node (ref "C96") (pin "1") (pinfunction "N1_1") (pintype "passive"))
      (node (ref "U18") (pin "1") (pinfunction "BOOT_1") (pintype "passive"))
    )
    (net (code "21") (name "Net-(C96-N2)") (class "Default")
      (node (ref "C96") (pin "2") (pinfunction "N2_2") (pintype "passive"))
      (node (ref "D1") (pin "1") (pinfunction "K_1") (pintype "passive"))
      (node (ref "L12") (pin "1") (pinfunction "N1_1") (pintype "passive"))
      (node (ref "U18") (pin "9") (pinfunction "SW_9") (pintype "passive"))
    )
    (net (code "22") (name "Net-(C100-N1)") (class "Default")
      (node (ref "C100") (pin "1") (pinfunction "N1_1") (pintype "passive"))
      (node (ref "C97") (pin "2") (pinfunction "N2_2") (pintype "passive"))
      (node (ref "C98") (pin "1") (pinfunction "N1_1") (pintype "passive"))
      (node (ref "C99") (pin "1") (pinfunction "N1_1") (pintype "passive"))
      (node (ref "L12") (pin "2") (pinfunction "N2_2") (pintype "passive"))
      (node (ref "R81") (pin "1") (pinfunction "1_1") (pintype "passive"))
      (node (ref "R82") (pin "2") (pinfunction "2_2") (pintype "passive"))
      (node (ref "TP12") (pin "1") (pinfunction "N1_1") (pintype "passive"))
    )
    (net (code "23") (name "Net-(C101-N2)") (class "Default")
      (node (ref "C101") (pin "2") (pinfunction "N2_2") (pintype "passive"))
      (node (ref "U18") (pin "4") (pinfunction "SS/TR_4") (pintype "passive"))
    )
    (net (code "24") (name "Net-(C102-N2)") (class "Default")
      (node (ref "C102") (pin "2") (pinfunction "N2_2") (pintype "passive"))
      (node (ref "R87") (pin "2") (pinfunction "2_2") (pintype "passive"))
      (node (ref "U18") (pin "7") (pinfunction "COMP_7") (pintype "passive"))
    )
    (net (code "25") (name "Net-(C103-N1)") (class "Default")
      (node (ref "C103") (pin "1") (pinfunction "N1_1") (pintype "passive"))
      (node (ref "R87") (pin "1") (pinfunction "1_1") (pintype "passive"))
    )
    (net (code "26") (name "Net-(J24-Pad4)") (class "Default")
      (node (ref "J24") (pin "4") (pinfunction "4_4") (pintype "passive"))
      (node (ref "R55") (pin "2") (pinfunction "2_2") (pintype "passive"))
    )
    (net (code "27") (name "Net-(J24-Pad6)") (class "Default")
      (node (ref "J24") (pin "6") (pinfunction "6_6") (pintype "passive"))
      (node (ref "R56") (pin "2") (pinfunction "2_2") (pintype "passive"))
    )
    (net (code "28") (name "Net-(J24-Pad8)") (class "Default")
      (node (ref "J24") (pin "8") (pinfunction "8_8") (pintype "passive"))
      (node (ref "R57") (pin "2") (pinfunction "2_2") (pintype "passive"))
    )
    (net (code "29") (name "Net-(J24-Pad10)") (class "Default")
      (node (ref "J24") (pin "10") (pinfunction "10_10") (pintype "passive"))
      (node (ref "R58") (pin "2") (pinfunction "2_2") (pintype "passive"))
    )
    (net (code "30") (name "Net-(J24-Pad14)") (class "Default")
      (node (ref "J24") (pin "14") (pinfunction "14_14") (pintype "passive"))
      (node (ref "R59") (pin "2") (pinfunction "2_2") (pintype "passive"))
    )
    (net (code "31") (name "Net-(J26-ID)") (class "Default")
      (node (ref "J26") (pin "4") (pinfunction "ID_4") (pintype "passive"))
      (node (ref "U12") (pin "6") (pinfunction "I/O_4_6") (pintype "passive"))
    )
    (net (code "32") (name "Net-(J26-Vbus)") (class "Default")
      (node (ref "J26") (pin "1") (pinfunction "Vbus_1") (pintype "passive"))
      (node (ref "R62") (pin "1") (pinfunction "1_1") (pintype "passive"))
      (node (ref "U12") (pin "2") (pinfunction "REF_1_2") (pintype "passive"))
    )
    (net (code "33") (name "Net-(LED2-A)") (class "Default")
      (node (ref "LED2") (pin "2") (pinfunction "A_2") (pintype "passive"))
      (node (ref "R65") (pin "2") (pinfunction "2_2") (pintype "passive"))
    )
    (net (code "34") (name "Net-(LED2-C)") (class "Default")
      (node (ref "LED2") (pin "1") (pinfunction "C_1") (pintype "passive"))
      (node (ref "Q5") (pin "3") (pinfunction "C_3") (pintype "passive"))
    )
    (net (code "35") (name "Net-(LED3-A)") (class "Default")
      (node (ref "LED3") (pin "2") (pinfunction "A_2") (pintype "passive"))
      (node (ref "R69") (pin "2") (pinfunction "2_2") (pintype "passive"))
    )
    (net (code "36") (name "Net-(LED3-C)") (class "Default")
      (node (ref "LED3") (pin "1") (pinfunction "C_1") (pintype "passive"))
      (node (ref "Q6") (pin "3") (pinfunction "C_3") (pintype "passive"))
    )
    (net (code "37") (name "Net-(Q5-B)") (class "Default")
      (node (ref "Q5") (pin "1") (pinfunction "B_1") (pintype "passive"))
      (node (ref "R68") (pin "1") (pinfunction "1_1") (pintype "passive"))
    )
    (net (code "38") (name "Net-(Q6-B)") (class "Default")
      (node (ref "Q6") (pin "1") (pinfunction "B_1") (pintype "passive"))
      (node (ref "R70") (pin "1") (pinfunction "1_1") (pintype "passive"))
    )
    (net (code "39") (name "Net-(Q7-GATE)") (class "Default")
      (node (ref "Q7") (pin "4") (pinfunction "GATE_4") (pintype "passive"))
      (node (ref "R78") (pin "2") (pinfunction "2_2") (pintype "passive"))
      (node (ref "R83") (pin "1") (pinfunction "1_1") (pintype "passive"))
    )
    (net (code "40") (name "Net-(Q8-DRAIN)") (class "Default")
      (node (ref "Q8") (pin "3") (pinfunction "DRAIN_3") (pintype "passive"))
      (node (ref "R83") (pin "2") (pinfunction "2_2") (pintype "passive"))
    )
    (net (code "41") (name "Net-(Q8-GATE)") (class "Default")
      (node (ref "Q8") (pin "1") (pinfunction "GATE_1") (pintype "passive"))
      (node (ref "R88") (pin "1") (pinfunction "1_1") (pintype "passive"))
      (node (ref "SW2") (pin "2") (pinfunction "2_2") (pintype "passive"))
    )
    (net (code "42") (name "Net-(R61-Pad1)") (class "Default")
      (node (ref "R61") (pin "1") (pinfunction "1_1") (pintype "passive"))
      (node (ref "SW1") (pin "1") (pinfunction "1_1") (pintype "passive"))
      (node (ref "SW1") (pin "2") (pinfunction "2_2") (pintype "passive"))
    )
    (net (code "43") (name "Net-(R84-Pad2)") (class "Default")
      (node (ref "R84") (pin "2") (pinfunction "2_2") (pintype "passive"))
      (node (ref "SW2") (pin "1") (pinfunction "1_1") (pintype "passive"))
    )
    (net (code "44") (name "Net-(TP11-N1)") (class "Default")
      (node (ref "R77") (pin "2") (pinfunction "2_2") (pintype "passive"))
      (node (ref "TP11") (pin "1") (pinfunction "N1_1") (pintype "passive"))
      (node (ref "U18") (pin "10") (pinfunction "PWRGD_10") (pintype "passive"))
    )
    (net (code "45") (name "Net-(U9-DET)") (class "Default")
      (node (ref "R62") (pin "2") (pinfunction "2_2") (pintype "passive"))
      (node (ref "R64") (pin "1") (pinfunction "1_1") (pintype "passive"))
      (node (ref "U9") (pin "18") (pinfunction "DET_18") (pintype "passive"))
    )
    (net (code "46") (name "Net-(U18-EN)") (class "Default")
      (node (ref "R79") (pin "1") (pinfunction "1_1") (pintype "passive"))
      (node (ref "R80") (pin "2") (pinfunction "2_2") (pintype "passive"))
      (node (ref "U18") (pin "3") (pinfunction "EN_3") (pintype "passive"))
    )
    (net (code "47") (name "Net-(U18-FB)") (class "Default")
      (node (ref "R82") (pin "1") (pinfunction "1_1") (pintype "passive"))
      (node (ref "R86") (pin "1") (pinfunction "1_1") (pintype "passive"))
      (node (ref "U18") (pin "6") (pinfunction "FB_6") (pintype "passive"))
    )
    (net (code "48") (name "Net-(U18-RT{slash}CLK)") (class "Default")
      (node (ref "R85") (pin "1") (pinfunction "1_1") (pintype "passive"))
      (node (ref "U18") (pin "5") (pinfunction "RT/CLK_5") (pintype "passive"))
    )
    (net (code "49") (name "VCC1V8") (class "Default")
      (node (ref "C79") (pin "1") (pinfunction "N1_1") (pintype "passive"))
      (node (ref "J24") (pin "2") (pinfunction "2_2") (pintype "passive"))
      (node (ref "R60") (pin "2") (pinfunction "2_2") (pintype "passive"))
      (node (ref "U9") (pin "8") (pinfunction "VREF_JTAG_8") (pintype "passive"))
    )
    (net (code "50") (name "VCC3V3") (class "Default")
      (node (ref "C75") (pin "1") (pinfunction "N1_1") (pintype "passive"))
      (node (ref "C76") (pin "1") (pinfunction "N1_1") (pintype "passive"))
      (node (ref "C78") (pin "1") (pinfunction "N1_1") (pintype "passive"))
      (node (ref "R63") (pin "1") (pinfunction "1_1") (pintype "passive"))
      (node (ref "R65") (pin "1") (pinfunction "1_1") (pintype "passive"))
      (node (ref "R69") (pin "1") (pinfunction "1_1") (pintype "passive"))
      (node (ref "U13") (pin "2") (pinfunction "OUT_2") (pintype "passive"))
      (node (ref "U9") (pin "15") (pinfunction "VDD_15") (pintype "passive"))
      (node (ref "U9") (pin "2") (pinfunction "VREF_UART_2") (pintype "passive"))
    )
    (net (code "51") (name "VCC3V3_DP") (class "Default")
      (node (ref "C84") (pin "1") (pinfunction "N1_1") (pintype "passive"))
      (node (ref "C85") (pin "1") (pinfunction "N1_1") (pintype "passive"))
      (node (ref "R71") (pin "2") (pinfunction "2_2") (pintype "passive"))
      (node (ref "U15") (pin "1") (pinfunction "OUT_1") (pintype "passive"))
      (node (ref "U15") (pin "2") (pinfunction "OUT_2") (pintype "passive"))
    )
    (net (code "52") (name "VCC4V8_LNA0") (class "Default")
      (node (ref "C87") (pin "1") (pinfunction "N1_1") (pintype "passive"))
      (node (ref "C88") (pin "1") (pinfunction "N1_1") (pintype "passive"))
      (node (ref "R73") (pin "2") (pinfunction "2_2") (pintype "passive"))
      (node (ref "U16") (pin "1") (pinfunction "OUT_1") (pintype "passive"))
      (node (ref "U16") (pin "2") (pinfunction "OUT_2") (pintype "passive"))
    )
    (net (code "53") (name "VCC4V8_LNA1") (class "Default")
      (node (ref "C90") (pin "1") (pinfunction "N1_1") (pintype "passive"))
      (node (ref "C91") (pin "1") (pinfunction "N1_1") (pintype "passive"))
      (node (ref "R75") (pin "2") (pinfunction "2_2") (pintype "passive"))
      (node (ref "U17") (pin "1") (pinfunction "OUT_1") (pintype "passive"))
      (node (ref "U17") (pin "2") (pinfunction "OUT_2") (pintype "passive"))
    )
    (net (code "54") (name "VCC5V0") (class "Default")
      (node (ref "C104") (pin "1") (pinfunction "N1_1") (pintype "passive"))
      (node (ref "C77") (pin "1") (pinfunction "N1_1") (pintype "passive"))
      (node (ref "C80") (pin "1") (pinfunction "N1_1") (pintype "passive"))
      (node (ref "C83") (pin "1") (pinfunction "N1_1") (pintype "passive"))
      (node (ref "C86") (pin "1") (pinfunction "N1_1") (pintype "passive"))
      (node (ref "C89") (pin "1") (pinfunction "N1_1") (pintype "passive"))
      (node (ref "J1") (pin "2") (pinfunction "2_2") (pintype "passive"))
      (node (ref "R77") (pin "1") (pinfunction "1_1") (pintype "passive"))
      (node (ref "R81") (pin "2") (pinfunction "2_2") (pintype "passive"))
      (node (ref "U13") (pin "3") (pinfunction "IN_3") (pintype "passive"))
      (node (ref "U14") (pin "7") (pinfunction "IN_7") (pintype "passive"))
      (node (ref "U14") (pin "8") (pinfunction "IN_8") (pintype "passive"))
      (node (ref "U14") (pin "9") (pinfunction "VCC_EPAD_9") (pintype "passive"))
      (node (ref "U15") (pin "7") (pinfunction "IN_7") (pintype "passive"))
      (node (ref "U15") (pin "8") (pinfunction "IN_8") (pintype "passive"))
      (node (ref "U15") (pin "9") (pinfunction "VCC_EPAD_9") (pintype "passive"))
      (node (ref "U16") (pin "7") (pinfunction "IN_7") (pintype "passive"))
      (node (ref "U16") (pin "8") (pinfunction "IN_8") (pintype "passive"))
      (node (ref "U16") (pin "9") (pinfunction "VCC_EPAD_9") (pintype "passive"))
      (node (ref "U17") (pin "7") (pinfunction "IN_7") (pintype "passive"))
      (node (ref "U17") (pin "8") (pinfunction "IN_8") (pintype "passive"))
      (node (ref "U17") (pin "9") (pinfunction "VCC_EPAD_9") (pintype "passive"))
    )
    (net (code "55") (name "VCC_RFCLK") (class "Default")
      (node (ref "C81") (pin "1") (pinfunction "N1_1") (pintype "passive"))
      (node (ref "C82") (pin "1") (pinfunction "N1_1") (pintype "passive"))
      (node (ref "R66") (pin "2") (pinfunction "2_2") (pintype "passive"))
      (node (ref "U14") (pin "1") (pinfunction "OUT_1") (pintype "passive"))
      (node (ref "U14") (pin "2") (pinfunction "OUT_2") (pintype "passive"))
    )
    (net (code "56") (name "unconnected-(J1-Pad3)") (class "Default")
      (node (ref "J1") (pin "3") (pinfunction "3_3") (pintype "passive+no_connect"))
    )
    (net (code "57") (name "unconnected-(J24-Pad12)") (class "Default")
      (node (ref "J24") (pin "12") (pinfunction "12_12") (pintype "passive+no_connect"))
    )
    (net (code "58") (name "unconnected-(U9-CTS-Pad3)") (class "Default")
      (node (ref "U9") (pin "3") (pinfunction "CTS_3") (pintype "passive+no_connect"))
    )
    (net (code "59") (name "unconnected-(U9-RTS-Pad4)") (class "Default")
      (node (ref "U9") (pin "4") (pinfunction "RTS_4") (pintype "passive+no_connect"))
    )
    (net (code "60") (name "unconnected-(U12-I{slash}O_1-Pad1)") (class "Default")
      (node (ref "U12") (pin "1") (pinfunction "I/O_1_1") (pintype "passive+no_connect"))
    )
    (net (code "61") (name "unconnected-(U14-NC-Pad4)") (class "Default")
      (node (ref "U14") (pin "4") (pinfunction "NC_4") (pintype "passive+no_connect"))
    )
    (net (code "62") (name "unconnected-(U15-NC-Pad4)") (class "Default")
      (node (ref "U15") (pin "4") (pinfunction "NC_4") (pintype "passive+no_connect"))
    )
    (net (code "63") (name "unconnected-(U16-NC-Pad4)") (class "Default")
      (node (ref "U16") (pin "4") (pinfunction "NC_4") (pintype "passive+no_connect"))
    )
    (net (code "64") (name "unconnected-(U17-NC-Pad4)") (class "Default")
      (node (ref "U17") (pin "4") (pinfunction "NC_4") (pintype "passive+no_connect"))
    )
  )
)
